# V1.net
KiCad netlist of a schematic drawn in EAGLE
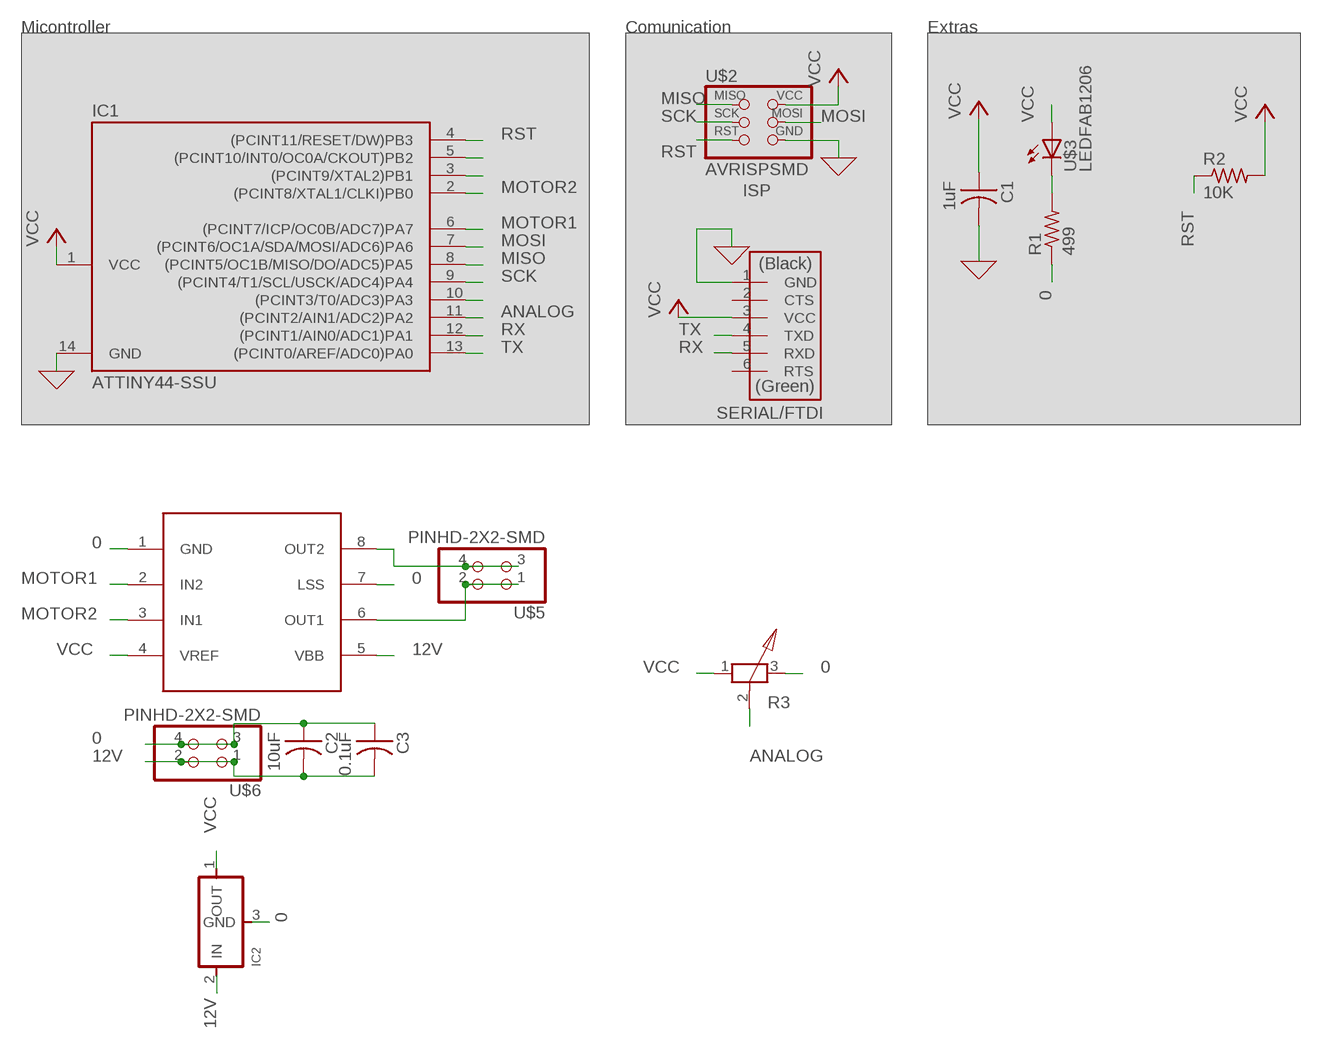
[diagram p0: schematic, sheet 1]

(export (version "E")
  (design (tool "Eeschema 10.0.6"))
  (components
    (comp (ref "C1")
      (value "1uF")
      (footprint "eagle-import:C1206FAB")
      (libsource (lib "eagle-import") (part "CAP-US1206FAB"))
    )
    (comp (ref "C2")
      (value "10uF")
      (footprint "eagle-import:C1206FAB")
      (libsource (lib "eagle-import") (part "CAP-US1206FAB"))
    )
    (comp (ref "C3")
      (value "0.1uF")
      (footprint "eagle-import:C1206FAB")
      (libsource (lib "eagle-import") (part "CAP-US1206FAB"))
    )
    (comp (ref "IC1")
      (value "ATTINY44-SSU")
      (footprint "eagle-import:SOIC14")
      (libsource (lib "eagle-import") (part "ATTINY44-SSU"))
    )
    (comp (ref "IC2")
      (value "REGULATORSOT23")
      (footprint "eagle-import:SOT23")
      (libsource (lib "eagle-import") (part "REGULATORSOT23"))
    )
    (comp (ref "R1")
      (value "499")
      (footprint "eagle-import:R1206FAB")
      (libsource (lib "eagle-import") (part "RES-US1206FAB"))
    )
    (comp (ref "R2")
      (value "10K")
      (footprint "eagle-import:R1206FAB")
      (libsource (lib "eagle-import") (part "RES-US1206FAB"))
    )
    (comp (ref "R3")
      (value "TRIMPOT")
      (footprint "eagle-import:SMDPOT")
      (libsource (lib "eagle-import") (part "TRIMPOT"))
    )
    (comp (ref "U$1")
      (value "FTDI-SMD-HEADER")
      (footprint "eagle-import:1X06SMD")
      (libsource (lib "eagle-import") (part "FTDI-SMD-HEADER"))
    )
    (comp (ref "U$2")
      (value "AVRISPSMD")
      (footprint "eagle-import:2X03SMD")
      (libsource (lib "eagle-import") (part "AVRISPSMD"))
    )
    (comp (ref "U$3")
      (value "LEDFAB1206")
      (footprint "eagle-import:LED1206FAB")
      (libsource (lib "eagle-import") (part "LEDFAB1206"))
    )
    (comp (ref "U$4")
      (value "A4953-H-BRIDGE-MOTOR-DRIVER")
      (footprint "eagle-import:SOIC8")
      (libsource (lib "eagle-import") (part "A4953-H-BRIDGE-MOTOR-DRIVER"))
    )
    (comp (ref "U$5")
      (value "PINHD-2X2-SMD")
      (footprint "eagle-import:2X02SMD")
      (libsource (lib "eagle-import") (part "PINHD-2X2-SMD"))
    )
    (comp (ref "U$6")
      (value "PINHD-2X2-SMD")
      (footprint "eagle-import:2X02SMD")
      (libsource (lib "eagle-import") (part "PINHD-2X2-SMD"))
    )
  )
  (nets
    (net (code "1") (name "/12V") (class "Default")
      (node (ref "C2") (pin "2") (pinfunction "2_2") (pintype "passive"))
      (node (ref "C3") (pin "2") (pinfunction "2_2") (pintype "passive"))
      (node (ref "IC2") (pin "2") (pinfunction "IN_2") (pintype "bidirectional"))
      (node (ref "U$4") (pin "5") (pinfunction "VBB_5") (pintype "bidirectional"))
      (node (ref "U$6") (pin "1") (pinfunction "1_1") (pintype "passive"))
      (node (ref "U$6") (pin "2") (pinfunction "2_2") (pintype "passive"))
    )
    (net (code "2") (name "/ANALOG") (class "Default")
      (node (ref "IC1") (pin "11") (pinfunction "(PCINT2/AIN1/ADC2)PA2_11") (pintype "bidirectional"))
      (node (ref "R3") (pin "2") (pinfunction "2_2") (pintype "passive"))
    )
    (net (code "3") (name "/MISO") (class "Default")
      (node (ref "IC1") (pin "8") (pinfunction "(PCINT5/OC1B/MISO/DO/ADC5)PA5_8") (pintype "bidirectional"))
      (node (ref "U$2") (pin "1") (pinfunction "MISO_1") (pintype "passive"))
    )
    (net (code "4") (name "/MOSI") (class "Default")
      (node (ref "IC1") (pin "7") (pinfunction "(PCINT6/OC1A/SDA/MOSI/ADC6)PA6_7") (pintype "bidirectional"))
      (node (ref "U$2") (pin "4") (pinfunction "MOSI_4") (pintype "passive"))
    )
    (net (code "5") (name "/MOTOR1") (class "Default")
      (node (ref "IC1") (pin "6") (pinfunction "(PCINT7/ICP/OC0B/ADC7)PA7_6") (pintype "bidirectional"))
      (node (ref "U$4") (pin "2") (pinfunction "IN2_2") (pintype "bidirectional"))
    )
    (net (code "6") (name "/MOTOR2") (class "Default")
      (node (ref "IC1") (pin "2") (pinfunction "(PCINT8/XTAL1/CLKI)PB0_2") (pintype "bidirectional"))
      (node (ref "U$4") (pin "3") (pinfunction "IN1_3") (pintype "bidirectional"))
    )
    (net (code "7") (name "/RST") (class "Default")
      (node (ref "IC1") (pin "4") (pinfunction "(PCINT11/RESET/DW)PB3_4") (pintype "bidirectional"))
      (node (ref "R2") (pin "1") (pinfunction "1_1") (pintype "passive"))
      (node (ref "U$2") (pin "5") (pinfunction "RST_5") (pintype "passive"))
    )
    (net (code "8") (name "/RX") (class "Default")
      (node (ref "IC1") (pin "12") (pinfunction "(PCINT1/AIN0/ADC1)PA1_12") (pintype "bidirectional"))
      (node (ref "U$1") (pin "5") (pinfunction "RXD_5") (pintype "bidirectional"))
    )
    (net (code "9") (name "/SCK") (class "Default")
      (node (ref "IC1") (pin "9") (pinfunction "(PCINT4/T1/SCL/USCK/ADC4)PA4_9") (pintype "bidirectional"))
      (node (ref "U$2") (pin "3") (pinfunction "SCK_3") (pintype "passive"))
    )
    (net (code "10") (name "/TX") (class "Default")
      (node (ref "IC1") (pin "13") (pinfunction "(PCINT0/AREF/ADC0)PA0_13") (pintype "bidirectional"))
      (node (ref "U$1") (pin "4") (pinfunction "TXD_4") (pintype "bidirectional"))
    )
    (net (code "11") (name "GND") (class "Default")
      (node (ref "C1") (pin "2") (pinfunction "2_2") (pintype "passive"))
      (node (ref "C2") (pin "1") (pinfunction "1_1") (pintype "passive"))
      (node (ref "C3") (pin "1") (pinfunction "1_1") (pintype "passive"))
      (node (ref "IC1") (pin "14") (pinfunction "GND_14") (pintype "power_in"))
      (node (ref "IC2") (pin "3") (pinfunction "GND_3") (pintype "bidirectional"))
      (node (ref "R1") (pin "1") (pinfunction "1_1") (pintype "passive"))
      (node (ref "R3") (pin "3") (pinfunction "3_3") (pintype "passive"))
      (node (ref "U$1") (pin "1") (pinfunction "GND_1") (pintype "bidirectional"))
      (node (ref "U$2") (pin "6") (pinfunction "GND_6") (pintype "passive"))
      (node (ref "U$4") (pin "1") (pinfunction "GND_1") (pintype "bidirectional"))
      (node (ref "U$4") (pin "7") (pinfunction "LSS_7") (pintype "bidirectional"))
      (node (ref "U$6") (pin "3") (pinfunction "3_3") (pintype "passive"))
      (node (ref "U$6") (pin "4") (pinfunction "4_4") (pintype "passive"))
    )
    (net (code "12") (name "Net-(U$3-C)") (class "Default")
      (node (ref "R1") (pin "2") (pinfunction "2_2") (pintype "passive"))
      (node (ref "U$3") (pin "2") (pinfunction "C_2") (pintype "passive"))
    )
    (net (code "13") (name "Net-(U$4-OUT1)") (class "Default")
      (node (ref "U$4") (pin "6") (pinfunction "OUT1_6") (pintype "bidirectional"))
      (node (ref "U$5") (pin "1") (pinfunction "1_1") (pintype "passive"))
      (node (ref "U$5") (pin "2") (pinfunction "2_2") (pintype "passive"))
    )
    (net (code "14") (name "Net-(U$4-OUT2)") (class "Default")
      (node (ref "U$4") (pin "8") (pinfunction "OUT2_8") (pintype "bidirectional"))
      (node (ref "U$5") (pin "3") (pinfunction "3_3") (pintype "passive"))
      (node (ref "U$5") (pin "4") (pinfunction "4_4") (pintype "passive"))
    )
    (net (code "15") (name "VCC") (class "Default")
      (node (ref "C1") (pin "1") (pinfunction "1_1") (pintype "passive"))
      (node (ref "IC1") (pin "1") (pinfunction "VCC_1") (pintype "power_in"))
      (node (ref "IC2") (pin "1") (pinfunction "OUT_1") (pintype "bidirectional"))
      (node (ref "R2") (pin "2") (pinfunction "2_2") (pintype "passive"))
      (node (ref "R3") (pin "1") (pinfunction "1_1") (pintype "passive"))
      (node (ref "U$1") (pin "3") (pinfunction "VCC_3") (pintype "bidirectional"))
      (node (ref "U$2") (pin "2") (pinfunction "VCC_2") (pintype "passive"))
      (node (ref "U$3") (pin "1") (pinfunction "A_1") (pintype "passive"))
      (node (ref "U$4") (pin "4") (pinfunction "VREF_4") (pintype "bidirectional"))
    )
    (net (code "16") (name "unconnected-(IC1-(PCINT3{slash}T0{slash}ADC3)PA3-Pad10)") (class "Default")
      (node (ref "IC1") (pin "10") (pinfunction "(PCINT3/T0/ADC3)PA3_10") (pintype "bidirectional"))
    )
    (net (code "17") (name "unconnected-(IC1-(PCINT9{slash}XTAL2)PB1-Pad3)") (class "Default")
      (node (ref "IC1") (pin "3") (pinfunction "(PCINT9/XTAL2)PB1_3") (pintype "bidirectional"))
    )
    (net (code "18") (name "unconnected-(IC1-(PCINT10{slash}INT0{slash}OC0A{slash}CKOUT)PB2-Pad5)") (class "Default")
      (node (ref "IC1") (pin "5") (pinfunction "(PCINT10/INT0/OC0A/CKOUT)PB2_5") (pintype "bidirectional"))
    )
    (net (code "19") (name "unconnected-(U$1-CTS-Pad2)") (class "Default")
      (node (ref "U$1") (pin "2") (pinfunction "CTS_2") (pintype "bidirectional"))
    )
    (net (code "20") (name "unconnected-(U$1-RTS-Pad6)") (class "Default")
      (node (ref "U$1") (pin "6") (pinfunction "RTS_6") (pintype "bidirectional"))
    )
  )
)
